# LED_Display.net
KiCad netlist of a schematic drawn in Altium Designer
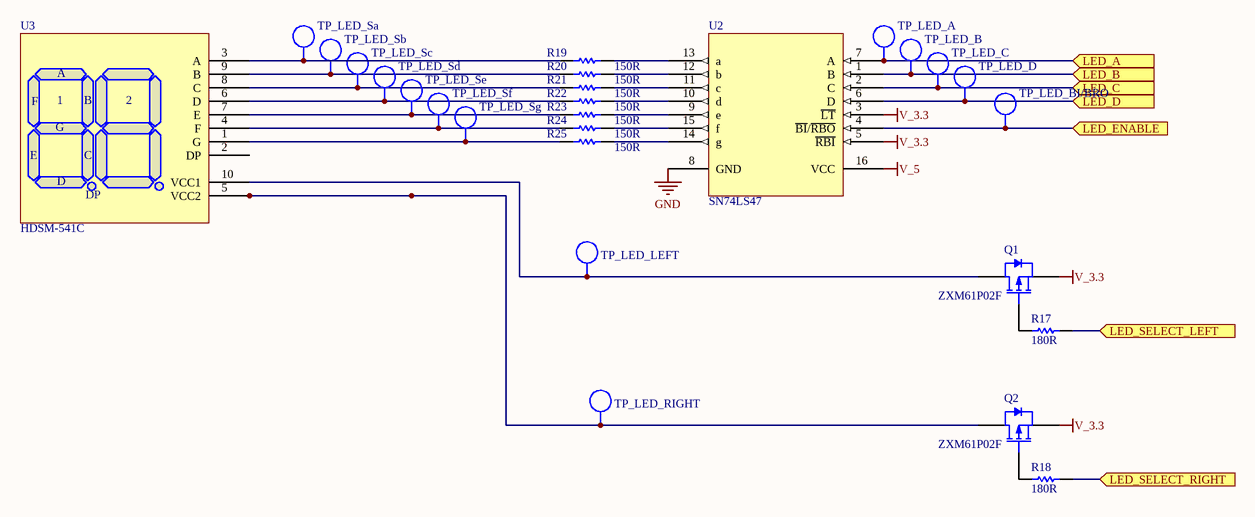
[diagram p0: LED_Display.SchDoc]

(export (version "E")
  (design (tool "Eeschema 10.0.6"))
  (components
    (comp (ref "Q1")
      (value "ZXM61P02F")
      (footprint "SOT23")
      (description "20V P-channel enhancement mode MOSFET")
      (fields (field (name "MANUFACTURER") "Zetex") (field (name "PART NUMBER") "TF_ZXM61P02F"))
      (libsource (lib "ENEL429_4") (part "TF_ZXM61P02F"))
    )
    (comp (ref "Q2")
      (value "ZXM61P02F")
      (footprint "SOT23")
      (description "20V P-channel enhancement mode MOSFET")
      (fields (field (name "MANUFACTURER") "Zetex") (field (name "PART NUMBER") "TF_ZXM61P02F"))
      (libsource (lib "ENEL429_4") (part "TF_ZXM61P02F"))
    )
    (comp (ref "R17")
      (value "180R")
      (footprint "0603")
      (description "RES 180OHM 1/10W 1% 0603 SMD")
      (fields (field (name "MANUFACTURER") "Panasonic - ECG") (field (name "PART NUMBER") "RS_180R 0603"))
      (libsource (lib "ENEL429_4") (part "RS_180R 0603"))
    )
    (comp (ref "R18")
      (value "180R")
      (footprint "0603")
      (description "RES 180OHM 1/10W 1% 0603 SMD")
      (fields (field (name "MANUFACTURER") "Panasonic - ECG") (field (name "PART NUMBER") "RS_180R 0603"))
      (libsource (lib "ENEL429_4") (part "RS_180R 0603"))
    )
    (comp (ref "R19")
      (value "150R")
      (footprint "0603")
      (description "RES 150 OHM 1/10W 1% 0603 SMD")
      (fields (field (name "MANUFACTURER") "ROHM") (field (name "PART NUMBER") "RS_150R 0603"))
      (libsource (lib "ENEL429_4") (part "RS_150R 0603"))
    )
    (comp (ref "R20")
      (value "150R")
      (footprint "0603")
      (description "RES 150 OHM 1/10W 1% 0603 SMD")
      (fields (field (name "MANUFACTURER") "ROHM") (field (name "PART NUMBER") "RS_150R 0603"))
      (libsource (lib "ENEL429_4") (part "RS_150R 0603"))
    )
    (comp (ref "R21")
      (value "150R")
      (footprint "0603")
      (description "RES 150 OHM 1/10W 1% 0603 SMD")
      (fields (field (name "MANUFACTURER") "ROHM") (field (name "PART NUMBER") "RS_150R 0603"))
      (libsource (lib "ENEL429_4") (part "RS_150R 0603"))
    )
    (comp (ref "R22")
      (value "150R")
      (footprint "0603")
      (description "RES 150 OHM 1/10W 1% 0603 SMD")
      (fields (field (name "MANUFACTURER") "ROHM") (field (name "PART NUMBER") "RS_150R 0603"))
      (libsource (lib "ENEL429_4") (part "RS_150R 0603"))
    )
    (comp (ref "R23")
      (value "150R")
      (footprint "0603")
      (description "RES 150 OHM 1/10W 1% 0603 SMD")
      (fields (field (name "MANUFACTURER") "ROHM") (field (name "PART NUMBER") "RS_150R 0603"))
      (libsource (lib "ENEL429_4") (part "RS_150R 0603"))
    )
    (comp (ref "R24")
      (value "150R")
      (footprint "0603")
      (description "RES 150 OHM 1/10W 1% 0603 SMD")
      (fields (field (name "MANUFACTURER") "ROHM") (field (name "PART NUMBER") "RS_150R 0603"))
      (libsource (lib "ENEL429_4") (part "RS_150R 0603"))
    )
    (comp (ref "R25")
      (value "150R")
      (footprint "0603")
      (description "RES 150 OHM 1/10W 1% 0603 SMD")
      (fields (field (name "MANUFACTURER") "ROHM") (field (name "PART NUMBER") "RS_150R 0603"))
      (libsource (lib "ENEL429_4") (part "RS_150R 0603"))
    )
    (comp (ref "TP_LED_A")
      (value "TP")
      (footprint "TEST_POINT_4X2MM")
      (description "Test-Point")
      (fields (field (name "PART NUMBER") "TP_TESTPOINT"))
      (libsource (lib "ENEL429_4") (part "TP_TESTPOINT"))
    )
    (comp (ref "TP_LED_B")
      (value "TP")
      (footprint "TEST_POINT_4X2MM")
      (description "Test-Point")
      (fields (field (name "PART NUMBER") "TP_TESTPOINT"))
      (libsource (lib "ENEL429_4") (part "TP_TESTPOINT"))
    )
    (comp (ref "TP_LED_BI/BRO")
      (value "TP")
      (footprint "TEST_POINT_4X2MM")
      (description "Test-Point")
      (fields (field (name "PART NUMBER") "TP_TESTPOINT"))
      (libsource (lib "ENEL429_4") (part "TP_TESTPOINT"))
    )
    (comp (ref "TP_LED_C")
      (value "TP")
      (footprint "TEST_POINT_4X2MM")
      (description "Test-Point")
      (fields (field (name "PART NUMBER") "TP_TESTPOINT"))
      (libsource (lib "ENEL429_4") (part "TP_TESTPOINT"))
    )
    (comp (ref "TP_LED_D")
      (value "TP")
      (footprint "TEST_POINT_4X2MM")
      (description "Test-Point")
      (fields (field (name "PART NUMBER") "TP_TESTPOINT"))
      (libsource (lib "ENEL429_4") (part "TP_TESTPOINT"))
    )
    (comp (ref "TP_LED_LEFT")
      (value "TP")
      (footprint "TEST_POINT_4X2MM")
      (description "Test-Point")
      (fields (field (name "PART NUMBER") "TP_TESTPOINT"))
      (libsource (lib "ENEL429_4") (part "TP_TESTPOINT"))
    )
    (comp (ref "TP_LED_RIGHT")
      (value "TP")
      (footprint "TEST_POINT_4X2MM")
      (description "Test-Point")
      (fields (field (name "PART NUMBER") "TP_TESTPOINT"))
      (libsource (lib "ENEL429_4") (part "TP_TESTPOINT"))
    )
    (comp (ref "TP_LED_Sa")
      (value "TP")
      (footprint "TEST_POINT_4X2MM")
      (description "Test-Point")
      (fields (field (name "PART NUMBER") "TP_TESTPOINT"))
      (libsource (lib "ENEL429_4") (part "TP_TESTPOINT"))
    )
    (comp (ref "TP_LED_Sb")
      (value "TP")
      (footprint "TEST_POINT_4X2MM")
      (description "Test-Point")
      (fields (field (name "PART NUMBER") "TP_TESTPOINT"))
      (libsource (lib "ENEL429_4") (part "TP_TESTPOINT"))
    )
    (comp (ref "TP_LED_Sc")
      (value "TP")
      (footprint "TEST_POINT_4X2MM")
      (description "Test-Point")
      (fields (field (name "PART NUMBER") "TP_TESTPOINT"))
      (libsource (lib "ENEL429_4") (part "TP_TESTPOINT"))
    )
    (comp (ref "TP_LED_Sd")
      (value "TP")
      (footprint "TEST_POINT_4X2MM")
      (description "Test-Point")
      (fields (field (name "PART NUMBER") "TP_TESTPOINT"))
      (libsource (lib "ENEL429_4") (part "TP_TESTPOINT"))
    )
    (comp (ref "TP_LED_Se")
      (value "TP")
      (footprint "TEST_POINT_4X2MM")
      (description "Test-Point")
      (fields (field (name "PART NUMBER") "TP_TESTPOINT"))
      (libsource (lib "ENEL429_4") (part "TP_TESTPOINT"))
    )
    (comp (ref "TP_LED_Sf")
      (value "TP")
      (footprint "TEST_POINT_4X2MM")
      (description "Test-Point")
      (fields (field (name "PART NUMBER") "TP_TESTPOINT"))
      (libsource (lib "ENEL429_4") (part "TP_TESTPOINT"))
    )
    (comp (ref "TP_LED_Sg")
      (value "TP")
      (footprint "TEST_POINT_4X2MM")
      (description "Test-Point")
      (fields (field (name "PART NUMBER") "TP_TESTPOINT"))
      (libsource (lib "ENEL429_4") (part "TP_TESTPOINT"))
    )
    (comp (ref "U2")
      (value "SN74LS47")
      (footprint "SOP127P780X200-16N")
      (fields (field (name "MANUFACTURER") "Texas Instruments"))
      (libsource (lib "Wacky_1") (part "SN74LS47"))
    )
    (comp (ref "U3")
      (value "HDSM-541C")
      (footprint "HDSM-541C")
      (description "2 character 7 segment display")
      (fields (field (name "MANUFACTURER") "AVAGO TECHNOLOGIES"))
      (libsource (lib "Wacky_1") (part "HDSM-541C"))
    )
  )
  (nets
    (net (code "1") (name "/LED_A") (class "Default")
      (node (ref "TP_LED_A") (pin "1") (pinfunction "1_1") (pintype "passive"))
      (node (ref "U2") (pin "7") (pinfunction "A_7") (pintype "input"))
    )
    (net (code "2") (name "/LED_B") (class "Default")
      (node (ref "TP_LED_B") (pin "1") (pinfunction "1_1") (pintype "passive"))
      (node (ref "U2") (pin "1") (pinfunction "B_1") (pintype "input"))
    )
    (net (code "3") (name "/LED_C") (class "Default")
      (node (ref "TP_LED_C") (pin "1") (pinfunction "1_1") (pintype "passive"))
      (node (ref "U2") (pin "2") (pinfunction "C_2") (pintype "input"))
    )
    (net (code "4") (name "/LED_D") (class "Default")
      (node (ref "TP_LED_D") (pin "1") (pinfunction "1_1") (pintype "passive"))
      (node (ref "U2") (pin "6") (pinfunction "D_6") (pintype "input"))
    )
    (net (code "5") (name "/LED_ENABLE") (class "Default")
      (node (ref "TP_LED_BI/BRO") (pin "1") (pinfunction "1_1") (pintype "passive"))
      (node (ref "U2") (pin "4") (pinfunction "~{BI}/~{RBO}_4") (pintype "input"))
    )
    (net (code "6") (name "/LED_SELECT_LEFT") (class "Default")
      (node (ref "R17") (pin "2") (pinfunction "2_2") (pintype "passive"))
    )
    (net (code "7") (name "/LED_SELECT_RIGHT") (class "Default")
      (node (ref "R18") (pin "2") (pinfunction "2_2") (pintype "passive"))
    )
    (net (code "8") (name "GND") (class "Default")
      (node (ref "U2") (pin "8") (pinfunction "GND_8") (pintype "passive"))
    )
    (net (code "9") (name "Net-(Q1-D)") (class "Default")
      (node (ref "Q1") (pin "3") (pinfunction "D_3") (pintype "passive"))
      (node (ref "TP_LED_LEFT") (pin "1") (pinfunction "1_1") (pintype "passive"))
      (node (ref "U3") (pin "10") (pinfunction "VCC1_10") (pintype "passive"))
    )
    (net (code "10") (name "Net-(Q1-G)") (class "Default")
      (node (ref "Q1") (pin "1") (pinfunction "G_1") (pintype "passive"))
      (node (ref "R17") (pin "1") (pinfunction "1_1") (pintype "passive"))
    )
    (net (code "11") (name "Net-(Q2-D)") (class "Default")
      (node (ref "Q2") (pin "3") (pinfunction "D_3") (pintype "passive"))
      (node (ref "TP_LED_RIGHT") (pin "1") (pinfunction "1_1") (pintype "passive"))
      (node (ref "U3") (pin "5") (pinfunction "VCC2_5") (pintype "passive"))
    )
    (net (code "12") (name "Net-(Q2-G)") (class "Default")
      (node (ref "Q2") (pin "1") (pinfunction "G_1") (pintype "passive"))
      (node (ref "R18") (pin "1") (pinfunction "1_1") (pintype "passive"))
    )
    (net (code "13") (name "Net-(U2-a)") (class "Default")
      (node (ref "R19") (pin "2") (pinfunction "2_2") (pintype "passive"))
      (node (ref "U2") (pin "13") (pinfunction "a_13") (pintype "output"))
    )
    (net (code "14") (name "Net-(U2-b)") (class "Default")
      (node (ref "R20") (pin "2") (pinfunction "2_2") (pintype "passive"))
      (node (ref "U2") (pin "12") (pinfunction "b_12") (pintype "output"))
    )
    (net (code "15") (name "Net-(U2-c)") (class "Default")
      (node (ref "R21") (pin "2") (pinfunction "2_2") (pintype "passive"))
      (node (ref "U2") (pin "11") (pinfunction "c_11") (pintype "output"))
    )
    (net (code "16") (name "Net-(U2-d)") (class "Default")
      (node (ref "R22") (pin "2") (pinfunction "2_2") (pintype "passive"))
      (node (ref "U2") (pin "10") (pinfunction "d_10") (pintype "output"))
    )
    (net (code "17") (name "Net-(U2-e)") (class "Default")
      (node (ref "R23") (pin "2") (pinfunction "2_2") (pintype "passive"))
      (node (ref "U2") (pin "9") (pinfunction "e_9") (pintype "output"))
    )
    (net (code "18") (name "Net-(U2-f)") (class "Default")
      (node (ref "R24") (pin "2") (pinfunction "2_2") (pintype "passive"))
      (node (ref "U2") (pin "15") (pinfunction "f_15") (pintype "output"))
    )
    (net (code "19") (name "Net-(U2-g)") (class "Default")
      (node (ref "R25") (pin "2") (pinfunction "2_2") (pintype "passive"))
      (node (ref "U2") (pin "14") (pinfunction "g_14") (pintype "output"))
    )
    (net (code "20") (name "Net-(U3-A)") (class "Default")
      (node (ref "R19") (pin "1") (pinfunction "1_1") (pintype "passive"))
      (node (ref "TP_LED_Sa") (pin "1") (pinfunction "1_1") (pintype "passive"))
      (node (ref "U3") (pin "3") (pinfunction "A_3") (pintype "passive"))
    )
    (net (code "21") (name "Net-(U3-B)") (class "Default")
      (node (ref "R20") (pin "1") (pinfunction "1_1") (pintype "passive"))
      (node (ref "TP_LED_Sb") (pin "1") (pinfunction "1_1") (pintype "passive"))
      (node (ref "U3") (pin "9") (pinfunction "B_9") (pintype "passive"))
    )
    (net (code "22") (name "Net-(U3-C)") (class "Default")
      (node (ref "R21") (pin "1") (pinfunction "1_1") (pintype "passive"))
      (node (ref "TP_LED_Sc") (pin "1") (pinfunction "1_1") (pintype "passive"))
      (node (ref "U3") (pin "8") (pinfunction "C_8") (pintype "passive"))
    )
    (net (code "23") (name "Net-(U3-D)") (class "Default")
      (node (ref "R22") (pin "1") (pinfunction "1_1") (pintype "passive"))
      (node (ref "TP_LED_Sd") (pin "1") (pinfunction "1_1") (pintype "passive"))
      (node (ref "U3") (pin "6") (pinfunction "D_6") (pintype "passive"))
    )
    (net (code "24") (name "Net-(U3-E)") (class "Default")
      (node (ref "R23") (pin "1") (pinfunction "1_1") (pintype "passive"))
      (node (ref "TP_LED_Se") (pin "1") (pinfunction "1_1") (pintype "passive"))
      (node (ref "U3") (pin "7") (pinfunction "E_7") (pintype "passive"))
    )
    (net (code "25") (name "Net-(U3-F)") (class "Default")
      (node (ref "R24") (pin "1") (pinfunction "1_1") (pintype "passive"))
      (node (ref "TP_LED_Sf") (pin "1") (pinfunction "1_1") (pintype "passive"))
      (node (ref "U3") (pin "4") (pinfunction "F_4") (pintype "passive"))
    )
    (net (code "26") (name "Net-(U3-G)") (class "Default")
      (node (ref "R25") (pin "1") (pinfunction "1_1") (pintype "passive"))
      (node (ref "TP_LED_Sg") (pin "1") (pinfunction "1_1") (pintype "passive"))
      (node (ref "U3") (pin "1") (pinfunction "G_1") (pintype "passive"))
    )
    (net (code "27") (name "V_3.3") (class "Default")
      (node (ref "Q1") (pin "2") (pinfunction "S_2") (pintype "passive"))
      (node (ref "Q2") (pin "2") (pinfunction "S_2") (pintype "passive"))
      (node (ref "U2") (pin "3") (pinfunction "~{LT}_3") (pintype "input"))
      (node (ref "U2") (pin "5") (pinfunction "~{RBI}_5") (pintype "input"))
    )
    (net (code "28") (name "V_5") (class "Default")
      (node (ref "U2") (pin "16") (pinfunction "VCC_16") (pintype "power_in"))
    )
    (net (code "29") (name "unconnected-(U3-DP-Pad2)") (class "Default")
      (node (ref "U3") (pin "2") (pinfunction "DP_2") (pintype "passive"))
    )
  )
)
